# Relays.net
KiCad netlist of a schematic drawn in Altium Designer
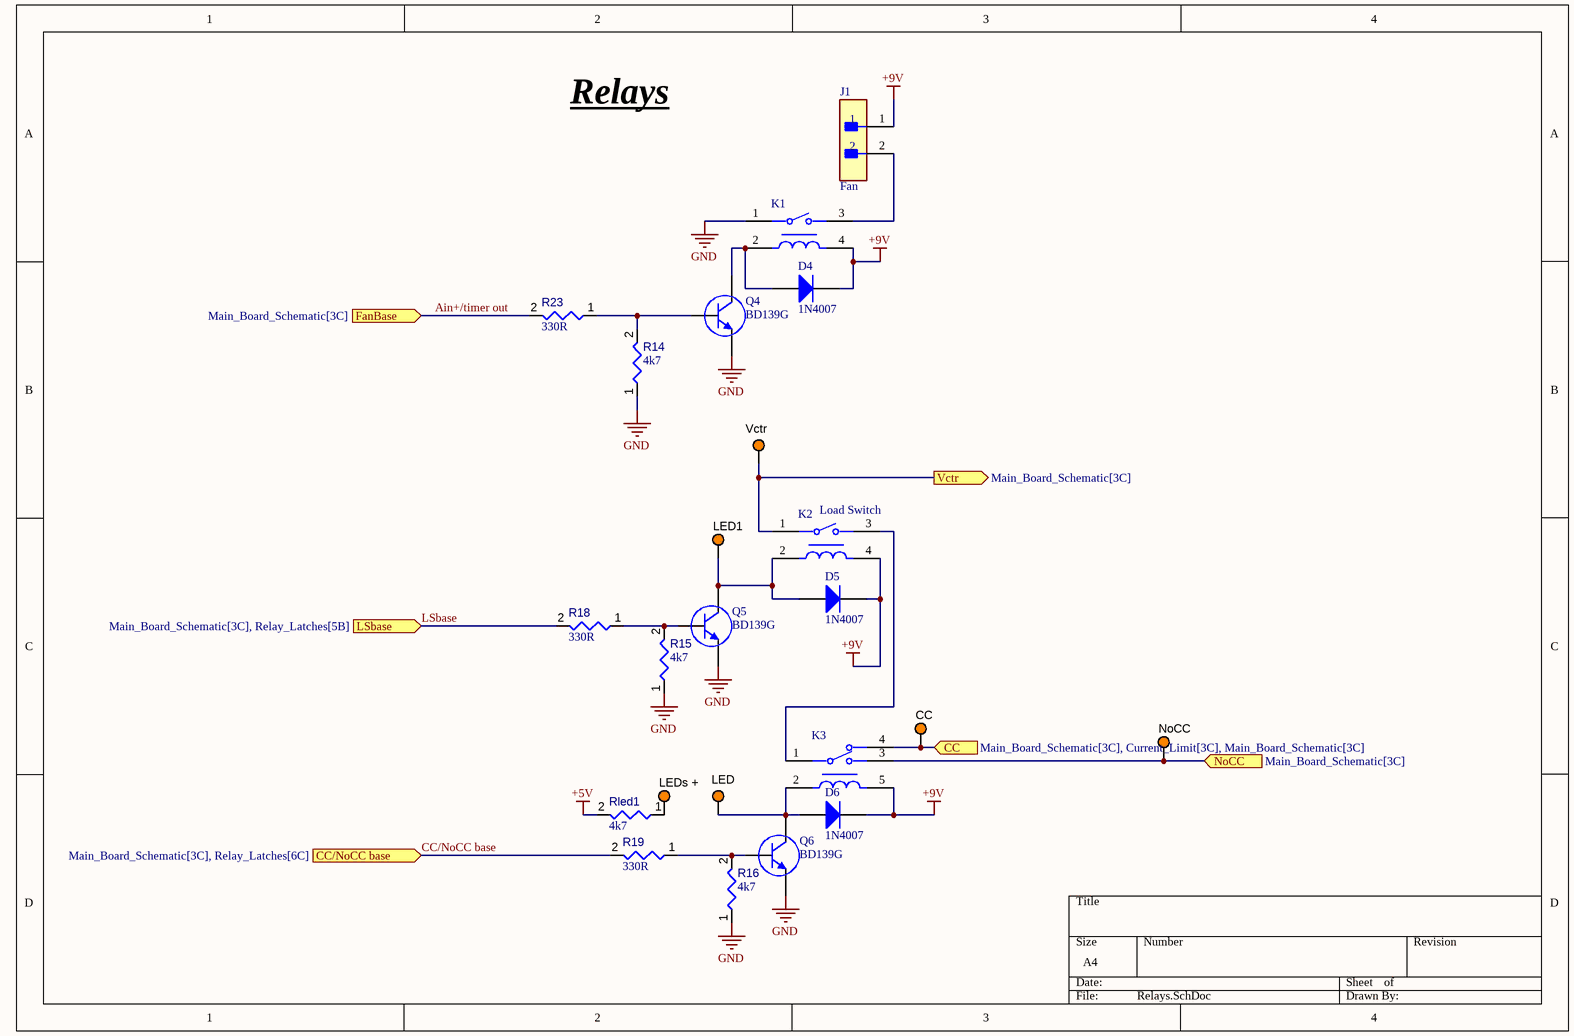
[diagram p0: Relays.SchDoc]

(export (version "E")
  (design (tool "Eeschema 10.0.6"))
  (components
    (comp (ref "CC")
      (value "5003")
      (footprint "KSTN-5003")
      (description "Test Point, Orange, Height 4.6 mm, Tail Length 3 mm, 1-Pin THD, RoHS")
      (fields (field (name "MANUFACTURER") "Keystone"))
      (libsource (lib "Konstantinos Psarras") (part "TESTPOINT_ORANGE"))
    )
    (comp (ref "D4")
      (value "1N4007")
      (footprint "FAIR-DO-41-2")
      (description "General Purpose Rectifier, 1.1 V, 1.0 A, -55 to 175 degC, 2-Pin DO-41, RoHS, Tape and Reel")
      (fields (field (name "MANUFACTURER") "Fairchild"))
      (libsource (lib "Konstantinos Psarras") (part "KESE-D_K1A2-2"))
    )
    (comp (ref "D5")
      (value "1N4007")
      (footprint "FAIR-DO-41-2")
      (description "General Purpose Rectifier, 1.1 V, 1.0 A, -55 to 175 degC, 2-Pin DO-41, RoHS, Tape and Reel")
      (fields (field (name "MANUFACTURER") "Fairchild"))
      (libsource (lib "Konstantinos Psarras") (part "KESE-D_K1A2-2"))
    )
    (comp (ref "D6")
      (value "1N4007")
      (footprint "FAIR-DO-41-2")
      (description "General Purpose Rectifier, 1.1 V, 1.0 A, -55 to 175 degC, 2-Pin DO-41, RoHS, Tape and Reel")
      (fields (field (name "MANUFACTURER") "Fairchild"))
      (libsource (lib "Konstantinos Psarras") (part "KESE-D_K1A2-2"))
    )
    (comp (ref "J1")
      (value "Fan")
      (footprint "FP-B2B-XH-A_LF_SN-MFG")
      (description "CONN HEADER VERT 2POS 2.5MM")
      (libsource (lib "Altium Content Vault") (part "3bc925449376181038e59eaffc5286c"))
    )
    (comp (ref "K1")
      (value "LKQ1AF-5V-TV-5")
      (footprint "FP-LKQ1AF-5V-TV-5-MFG")
      (description "Quiet Type, High Sensitivity 250MW, Slim Power Relay")
      (libsource (lib "Konstantinos Psarras") (part "efdf740da079d6e8343da2175463948"))
    )
    (comp (ref "K2")
      (value "Load Switch")
      (footprint "FP-LKQ1AF-5V-TV-5-MFG")
      (description "Quiet Type, High Sensitivity 250MW, Slim Power Relay")
      (libsource (lib "Konstantinos Psarras") (part "efdf740da079d6e8343da2175463948"))
    )
    (comp (ref "K3")
      (value "G5LE-14-36 DC12")
      (footprint "FP-G5LE-14-36_DC12-MFG")
      (description "RELAY GEN PURPOSE SPDT 10A 12V")
      (libsource (lib "Altium Content Vault") (part "c03b8d08e5d02e70a6880f365e34168"))
    )
    (comp (ref "LED")
      (value "5003")
      (footprint "KSTN-5003")
      (description "Test Point, Orange, Height 4.6 mm, Tail Length 3 mm, 1-Pin THD, RoHS")
      (fields (field (name "MANUFACTURER") "Keystone"))
      (libsource (lib "Konstantinos Psarras") (part "TESTPOINT_ORANGE"))
    )
    (comp (ref "LED1")
      (value "5003")
      (footprint "KSTN-5003")
      (description "Test Point, Orange, Height 4.6 mm, Tail Length 3 mm, 1-Pin THD, RoHS")
      (fields (field (name "MANUFACTURER") "Keystone"))
      (libsource (lib "Konstantinos Psarras") (part "TESTPOINT_ORANGE"))
    )
    (comp (ref "LEDs +")
      (value "5003")
      (footprint "KSTN-5003")
      (description "Test Point, Orange, Height 4.6 mm, Tail Length 3 mm, 1-Pin THD, RoHS")
      (fields (field (name "MANUFACTURER") "Keystone"))
      (libsource (lib "Konstantinos Psarras") (part "TESTPOINT_ORANGE"))
    )
    (comp (ref "NoCC")
      (value "5003")
      (footprint "KSTN-5003")
      (description "Test Point, Orange, Height 4.6 mm, Tail Length 3 mm, 1-Pin THD, RoHS")
      (fields (field (name "MANUFACTURER") "Keystone"))
      (libsource (lib "Konstantinos Psarras") (part "TESTPOINT_ORANGE"))
    )
    (comp (ref "Q4")
      (value "BD139G")
      (footprint "FP-77-09-MFG")
      (description "1.5 A, 80 V NPN Power Bipolar Junction Transistor. ONSSPCTRNSTLT1T0R;")
      (libsource (lib "Konstantinos Psarras") (part "TRANS-NPN-3"))
    )
    (comp (ref "Q5")
      (value "BD139G")
      (footprint "FP-77-09-MFG")
      (description "1.5 A, 80 V NPN Power Bipolar Junction Transistor. ONSSPCTRNSTLT1T0R;")
      (libsource (lib "Konstantinos Psarras") (part "TRANS-NPN-3"))
    )
    (comp (ref "Q6")
      (value "BD139G")
      (footprint "FP-77-09-MFG")
      (description "1.5 A, 80 V NPN Power Bipolar Junction Transistor. ONSSPCTRNSTLT1T0R;")
      (libsource (lib "Konstantinos Psarras") (part "TRANS-NPN-3"))
    )
    (comp (ref "R14")
      (value "4k7")
      (footprint "RESA60-630X240")
      (description "Axial Resistor, 100 Ohm, +/- 1%, 0.25 W, -55 to 155 degC, 2-Pin THD, RoHS, Bulk")
      (fields (field (name "MANUFACTURER") "Yageo") (field (name "TOLERANCE") "1%"))
      (libsource (lib "Konstantinos Psarras") (part "RES-2"))
    )
    (comp (ref "R15")
      (value "4k7")
      (footprint "RESA60-630X240")
      (description "Axial Resistor, 100 Ohm, +/- 1%, 0.25 W, -55 to 155 degC, 2-Pin THD, RoHS, Bulk")
      (fields (field (name "MANUFACTURER") "Yageo") (field (name "TOLERANCE") "1%"))
      (libsource (lib "Konstantinos Psarras") (part "RES-2"))
    )
    (comp (ref "R16")
      (value "4k7")
      (footprint "RESA60-630X240")
      (description "Axial Resistor, 100 Ohm, +/- 1%, 0.25 W, -55 to 155 degC, 2-Pin THD, RoHS, Bulk")
      (fields (field (name "MANUFACTURER") "Yageo") (field (name "TOLERANCE") "1%"))
      (libsource (lib "Konstantinos Psarras") (part "RES-2"))
    )
    (comp (ref "R18")
      (value "330R")
      (footprint "RESA60-630X240")
      (description "Axial Resistor, 100 Ohm, +/- 1%, 0.25 W, -55 to 155 degC, 2-Pin THD, RoHS, Bulk")
      (fields (field (name "MANUFACTURER") "Yageo") (field (name "TOLERANCE") "1%"))
      (libsource (lib "Konstantinos Psarras") (part "RES-2"))
    )
    (comp (ref "R19")
      (value "330R")
      (footprint "RESA60-630X240")
      (description "Axial Resistor, 100 Ohm, +/- 1%, 0.25 W, -55 to 155 degC, 2-Pin THD, RoHS, Bulk")
      (fields (field (name "MANUFACTURER") "Yageo") (field (name "TOLERANCE") "1%"))
      (libsource (lib "Konstantinos Psarras") (part "RES-2"))
    )
    (comp (ref "R23")
      (value "330R")
      (footprint "RESA60-630X240")
      (description "Axial Resistor, 100 Ohm, +/- 1%, 0.25 W, -55 to 155 degC, 2-Pin THD, RoHS, Bulk")
      (fields (field (name "MANUFACTURER") "Yageo") (field (name "TOLERANCE") "1%"))
      (libsource (lib "Konstantinos Psarras") (part "RES-2"))
    )
    (comp (ref "Rled1")
      (value "4k7")
      (footprint "RESA60-630X240")
      (description "Axial Resistor, 100 Ohm, +/- 1%, 0.25 W, -55 to 155 degC, 2-Pin THD, RoHS, Bulk")
      (fields (field (name "MANUFACTURER") "Yageo") (field (name "TOLERANCE") "1%"))
      (libsource (lib "Konstantinos Psarras") (part "RES-2"))
    )
    (comp (ref "Vctr")
      (value "5003")
      (footprint "KSTN-5003")
      (description "Test Point, Orange, Height 4.6 mm, Tail Length 3 mm, 1-Pin THD, RoHS")
      (fields (field (name "MANUFACTURER") "Keystone"))
      (libsource (lib "Konstantinos Psarras") (part "TESTPOINT_ORANGE"))
    )
  )
  (nets
    (net (code "1") (name "+5V") (class "Default")
      (node (ref "Rled1") (pin "2") (pinfunction "2_2") (pintype "passive"))
    )
    (net (code "2") (name "+9V") (class "Default")
      (node (ref "D4") (pin "1") (pinfunction "K_1") (pintype "passive"))
      (node (ref "D5") (pin "1") (pinfunction "K_1") (pintype "passive"))
      (node (ref "D6") (pin "1") (pinfunction "K_1") (pintype "passive"))
      (node (ref "J1") (pin "1") (pinfunction "1_1") (pintype "passive"))
      (node (ref "K1") (pin "4") (pinfunction "4_4") (pintype "passive"))
      (node (ref "K2") (pin "4") (pinfunction "4_4") (pintype "passive"))
      (node (ref "K3") (pin "5") (pinfunction "5_5") (pintype "passive"))
    )
    (net (code "3") (name "/Ain+{slash}timer out") (class "Default")
      (node (ref "R23") (pin "2") (pinfunction "2_2") (pintype "passive"))
    )
    (net (code "4") (name "/CC") (class "Default")
      (node (ref "CC") (pin "1") (pinfunction "1_1") (pintype "passive"))
      (node (ref "K3") (pin "4") (pinfunction "4_4") (pintype "passive"))
    )
    (net (code "5") (name "/CC{slash}NoCC base") (class "Default")
      (node (ref "R19") (pin "2") (pinfunction "2_2") (pintype "passive"))
    )
    (net (code "6") (name "/LSbase") (class "Default")
      (node (ref "R18") (pin "2") (pinfunction "2_2") (pintype "passive"))
    )
    (net (code "7") (name "/NoCC") (class "Default")
      (node (ref "K3") (pin "3") (pinfunction "3_3") (pintype "passive"))
      (node (ref "NoCC") (pin "1") (pinfunction "1_1") (pintype "passive"))
    )
    (net (code "8") (name "/Vctr") (class "Default")
      (node (ref "K2") (pin "1") (pinfunction "1_1") (pintype "passive"))
      (node (ref "Vctr") (pin "1") (pinfunction "1_1") (pintype "passive"))
    )
    (net (code "9") (name "GND") (class "Default")
      (node (ref "K1") (pin "1") (pinfunction "1_1") (pintype "passive"))
      (node (ref "Q4") (pin "1") (pinfunction "E_1") (pintype "passive"))
      (node (ref "Q5") (pin "1") (pinfunction "E_1") (pintype "passive"))
      (node (ref "Q6") (pin "1") (pinfunction "E_1") (pintype "passive"))
      (node (ref "R14") (pin "1") (pinfunction "1_1") (pintype "passive"))
      (node (ref "R15") (pin "1") (pinfunction "1_1") (pintype "passive"))
      (node (ref "R16") (pin "1") (pinfunction "1_1") (pintype "passive"))
    )
    (net (code "10") (name "Net-(D4-A)") (class "Default")
      (node (ref "D4") (pin "2") (pinfunction "A_2") (pintype "passive"))
      (node (ref "K1") (pin "2") (pinfunction "2_2") (pintype "passive"))
      (node (ref "Q4") (pin "3") (pinfunction "C_3") (pintype "passive"))
    )
    (net (code "11") (name "Net-(D5-A)") (class "Default")
      (node (ref "D5") (pin "2") (pinfunction "A_2") (pintype "passive"))
      (node (ref "K2") (pin "2") (pinfunction "2_2") (pintype "passive"))
      (node (ref "LED1") (pin "1") (pinfunction "1_1") (pintype "passive"))
      (node (ref "Q5") (pin "3") (pinfunction "C_3") (pintype "passive"))
    )
    (net (code "12") (name "Net-(D6-A)") (class "Default")
      (node (ref "D6") (pin "2") (pinfunction "A_2") (pintype "passive"))
      (node (ref "K3") (pin "2") (pinfunction "2_2") (pintype "passive"))
      (node (ref "LED") (pin "1") (pinfunction "1_1") (pintype "passive"))
      (node (ref "Q6") (pin "3") (pinfunction "C_3") (pintype "passive"))
    )
    (net (code "13") (name "Net-(J1-Pad2)") (class "Default")
      (node (ref "J1") (pin "2") (pinfunction "2_2") (pintype "passive"))
      (node (ref "K1") (pin "3") (pinfunction "3_3") (pintype "passive"))
    )
    (net (code "14") (name "Net-(K2-Pad3)") (class "Default")
      (node (ref "K2") (pin "3") (pinfunction "3_3") (pintype "passive"))
      (node (ref "K3") (pin "1") (pinfunction "1_1") (pintype "passive"))
    )
    (net (code "15") (name "Net-(LEDs +-Pad1)") (class "Default")
      (node (ref "LEDs +") (pin "1") (pinfunction "1_1") (pintype "passive"))
      (node (ref "Rled1") (pin "1") (pinfunction "1_1") (pintype "passive"))
    )
    (net (code "16") (name "Net-(Q4-B)") (class "Default")
      (node (ref "Q4") (pin "2") (pinfunction "B_2") (pintype "passive"))
      (node (ref "R14") (pin "2") (pinfunction "2_2") (pintype "passive"))
      (node (ref "R23") (pin "1") (pinfunction "1_1") (pintype "passive"))
    )
    (net (code "17") (name "Net-(Q5-B)") (class "Default")
      (node (ref "Q5") (pin "2") (pinfunction "B_2") (pintype "passive"))
      (node (ref "R15") (pin "2") (pinfunction "2_2") (pintype "passive"))
      (node (ref "R18") (pin "1") (pinfunction "1_1") (pintype "passive"))
    )
    (net (code "18") (name "Net-(Q6-B)") (class "Default")
      (node (ref "Q6") (pin "2") (pinfunction "B_2") (pintype "passive"))
      (node (ref "R16") (pin "2") (pinfunction "2_2") (pintype "passive"))
      (node (ref "R19") (pin "1") (pinfunction "1_1") (pintype "passive"))
    )
  )
)
